# N64A_FA.net
KiCad netlist of a schematic drawn in EAGLE
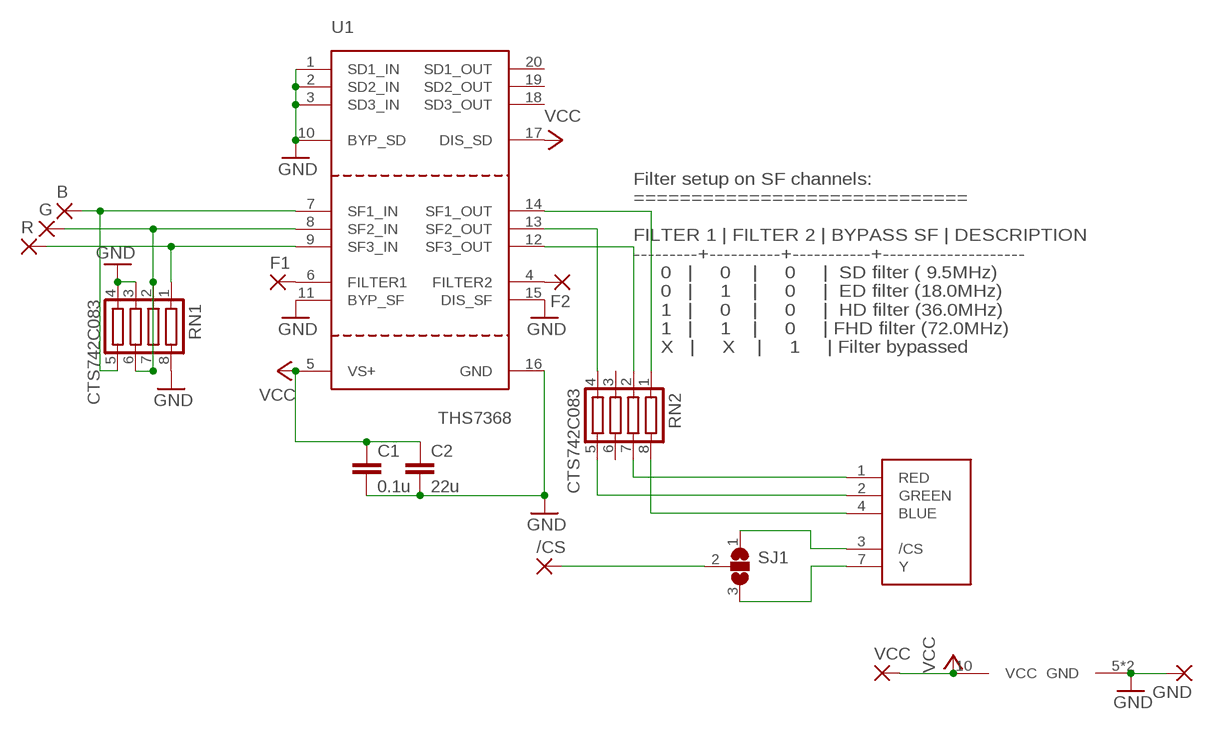
[diagram p0: schematic, sheet 1]

(export (version "E")
  (design (tool "Eeschema 10.0.6"))
  (components
    (comp (ref "/CS")
      (value "SMD2")
      (footprint "eagle-import:SMD1,27-2,54")
      (libsource (lib "eagle-import") (part "SMD2"))
    )
    (comp (ref "B")
      (value "SMD2")
      (footprint "eagle-import:SMD1,27-2,54")
      (libsource (lib "eagle-import") (part "SMD2"))
    )
    (comp (ref "C1")
      (value "0.1u")
      (footprint "eagle-import:C0603")
      (libsource (lib "eagle-import") (part "C-EUC0603"))
    )
    (comp (ref "C2")
      (value "22u")
      (footprint "eagle-import:C1206")
      (libsource (lib "eagle-import") (part "C-EUC1206"))
    )
    (comp (ref "F1")
      (value "SMD1")
      (footprint "eagle-import:SMD0,8-1,6")
      (libsource (lib "eagle-import") (part "SMD1"))
    )
    (comp (ref "F2")
      (value "SMD1")
      (footprint "eagle-import:SMD0,8-1,6")
      (libsource (lib "eagle-import") (part "SMD1"))
    )
    (comp (ref "G")
      (value "SMD2")
      (footprint "eagle-import:SMD1,27-2,54")
      (libsource (lib "eagle-import") (part "SMD2"))
    )
    (comp (ref "GND")
      (value "SMD2")
      (footprint "eagle-import:SMD1,27-2,54")
      (libsource (lib "eagle-import") (part "SMD2"))
    )
    (comp (ref "R")
      (value "SMD2")
      (footprint "eagle-import:SMD1,27-2,54")
      (libsource (lib "eagle-import") (part "SMD2"))
    )
    (comp (ref "RN1")
      (value "CTS742C083")
      (footprint "eagle-import:CTS742C083")
      (libsource (lib "eagle-import") (part "CTS742C083"))
    )
    (comp (ref "RN2")
      (value "CTS742C083")
      (footprint "eagle-import:CTS742C083")
      (libsource (lib "eagle-import") (part "CTS742C083"))
    )
    (comp (ref "SJ1")
      (value "SJ2W")
      (footprint "eagle-import:SJ_2")
      (libsource (lib "eagle-import") (part "SJ2W"))
    )
    (comp (ref "U$1")
      (value "SNES_MULTIAV_RGBSY")
      (footprint "eagle-import:SNES_MULTIAV_RGBSY")
      (libsource (lib "eagle-import") (part "SNES_MULTIAV_RGBSY"))
    )
    (comp (ref "U1")
      (value "THS7368")
      (footprint "eagle-import:THS7368")
      (libsource (lib "eagle-import") (part "THS7368"))
    )
    (comp (ref "VCC")
      (value "SMD2")
      (footprint "eagle-import:SMD1,27-2,54")
      (libsource (lib "eagle-import") (part "SMD2"))
    )
  )
  (nets
    (net (code "1") (name "GND") (class "Default")
      (node (ref "C1") (pin "2") (pinfunction "2_2") (pintype "passive"))
      (node (ref "C2") (pin "2") (pinfunction "2_2") (pintype "passive"))
      (node (ref "GND") (pin "1") (pinfunction "P_1") (pintype "passive"))
      (node (ref "RN1") (pin "3") (pinfunction "3_3") (pintype "passive"))
      (node (ref "RN1") (pin "4") (pinfunction "4_4") (pintype "passive"))
      (node (ref "RN1") (pin "8") (pinfunction "8_8") (pintype "passive"))
      (node (ref "U$1") (pin "5") (pinfunction "GND_5") (pintype "bidirectional"))
      (node (ref "U$1") (pin "6") (pinfunction "GND_6") (pintype "bidirectional"))
      (node (ref "U1") (pin "1") (pinfunction "SD1_IN_1") (pintype "input"))
      (node (ref "U1") (pin "10") (pinfunction "BYP_SD_10") (pintype "input"))
      (node (ref "U1") (pin "11") (pinfunction "BYP_SF_11") (pintype "input"))
      (node (ref "U1") (pin "15") (pinfunction "DIS_SF_15") (pintype "input"))
      (node (ref "U1") (pin "16") (pinfunction "GND_16") (pintype "power_in"))
      (node (ref "U1") (pin "2") (pinfunction "SD2_IN_2") (pintype "input"))
      (node (ref "U1") (pin "3") (pinfunction "SD3_IN_3") (pintype "input"))
    )
    (net (code "2") (name "Net-(/CS-P)") (class "Default")
      (node (ref "/CS") (pin "1") (pinfunction "P_1") (pintype "passive"))
      (node (ref "SJ1") (pin "2") (pinfunction "2_2") (pintype "passive"))
    )
    (net (code "3") (name "Net-(B-P)") (class "Default")
      (node (ref "B") (pin "1") (pinfunction "P_1") (pintype "passive"))
      (node (ref "RN1") (pin "5") (pinfunction "5_5") (pintype "passive"))
      (node (ref "U1") (pin "7") (pinfunction "SF1_IN_7") (pintype "input"))
    )
    (net (code "4") (name "Net-(F1-P)") (class "Default")
      (node (ref "F1") (pin "P$1") (pinfunction "P_P$1") (pintype "passive"))
      (node (ref "U1") (pin "6") (pinfunction "FILTER1_6") (pintype "input"))
    )
    (net (code "5") (name "Net-(F2-P)") (class "Default")
      (node (ref "F2") (pin "P$1") (pinfunction "P_P$1") (pintype "passive"))
      (node (ref "U1") (pin "4") (pinfunction "FILTER2_4") (pintype "input"))
    )
    (net (code "6") (name "Net-(G-P)") (class "Default")
      (node (ref "G") (pin "1") (pinfunction "P_1") (pintype "passive"))
      (node (ref "RN1") (pin "2") (pinfunction "2_2") (pintype "passive"))
      (node (ref "RN1") (pin "6") (pinfunction "6_6") (pintype "passive"))
      (node (ref "RN1") (pin "7") (pinfunction "7_7") (pintype "passive"))
      (node (ref "U1") (pin "8") (pinfunction "SF2_IN_8") (pintype "input"))
    )
    (net (code "7") (name "Net-(R-P)") (class "Default")
      (node (ref "R") (pin "1") (pinfunction "P_1") (pintype "passive"))
      (node (ref "RN1") (pin "1") (pinfunction "1_1") (pintype "passive"))
      (node (ref "U1") (pin "9") (pinfunction "SF3_IN_9") (pintype "input"))
    )
    (net (code "8") (name "Net-(U$1A-BLUE)") (class "Default")
      (node (ref "RN2") (pin "8") (pinfunction "8_8") (pintype "passive"))
      (node (ref "U$1") (pin "4") (pinfunction "BLUE_4") (pintype "bidirectional"))
    )
    (net (code "9") (name "Net-(U$1A-GREEN)") (class "Default")
      (node (ref "RN2") (pin "5") (pinfunction "5_5") (pintype "passive"))
      (node (ref "U$1") (pin "2") (pinfunction "GREEN_2") (pintype "bidirectional"))
    )
    (net (code "10") (name "Net-(U$1A-RED)") (class "Default")
      (node (ref "RN2") (pin "7") (pinfunction "7_7") (pintype "passive"))
      (node (ref "U$1") (pin "1") (pinfunction "RED_1") (pintype "bidirectional"))
    )
    (net (code "11") (name "Net-(U$1A-Y)") (class "Default")
      (node (ref "SJ1") (pin "3") (pinfunction "3_3") (pintype "passive"))
      (node (ref "U$1") (pin "7") (pinfunction "Y_7") (pintype "bidirectional"))
    )
    (net (code "12") (name "Net-(U$1A-{slash}CS)") (class "Default")
      (node (ref "SJ1") (pin "1") (pinfunction "1_1") (pintype "passive"))
      (node (ref "U$1") (pin "3") (pinfunction "/CS_3") (pintype "bidirectional"))
    )
    (net (code "13") (name "Net-(U1-SF1_OUT)") (class "Default")
      (node (ref "RN2") (pin "1") (pinfunction "1_1") (pintype "passive"))
      (node (ref "U1") (pin "14") (pinfunction "SF1_OUT_14") (pintype "output"))
    )
    (net (code "14") (name "Net-(U1-SF2_OUT)") (class "Default")
      (node (ref "RN2") (pin "4") (pinfunction "4_4") (pintype "passive"))
      (node (ref "U1") (pin "13") (pinfunction "SF2_OUT_13") (pintype "output"))
    )
    (net (code "15") (name "Net-(U1-SF3_OUT)") (class "Default")
      (node (ref "RN2") (pin "2") (pinfunction "2_2") (pintype "passive"))
      (node (ref "U1") (pin "12") (pinfunction "SF3_OUT_12") (pintype "output"))
    )
    (net (code "16") (name "VCC") (class "Default")
      (node (ref "C1") (pin "1") (pinfunction "1_1") (pintype "passive"))
      (node (ref "C2") (pin "1") (pinfunction "1_1") (pintype "passive"))
      (node (ref "U$1") (pin "10") (pinfunction "VCC_10") (pintype "bidirectional"))
      (node (ref "U1") (pin "17") (pinfunction "DIS_SD_17") (pintype "input"))
      (node (ref "U1") (pin "5") (pinfunction "VS+_5") (pintype "power_in"))
      (node (ref "VCC") (pin "1") (pinfunction "P_1") (pintype "passive"))
    )
    (net (code "17") (name "unconnected-(RN2-Pad3)") (class "Default")
      (node (ref "RN2") (pin "3") (pinfunction "3_3") (pintype "passive"))
    )
    (net (code "18") (name "unconnected-(RN2-Pad6)") (class "Default")
      (node (ref "RN2") (pin "6") (pinfunction "6_6") (pintype "passive"))
    )
    (net (code "19") (name "unconnected-(U1-SD1_OUT-Pad20)") (class "Default")
      (node (ref "U1") (pin "20") (pinfunction "SD1_OUT_20") (pintype "output"))
    )
    (net (code "20") (name "unconnected-(U1-SD2_OUT-Pad19)") (class "Default")
      (node (ref "U1") (pin "19") (pinfunction "SD2_OUT_19") (pintype "output"))
    )
    (net (code "21") (name "unconnected-(U1-SD3_OUT-Pad18)") (class "Default")
      (node (ref "U1") (pin "18") (pinfunction "SD3_OUT_18") (pintype "output"))
    )
  )
)
